# Main.net
KiCad netlist of a schematic drawn in Altium Designer
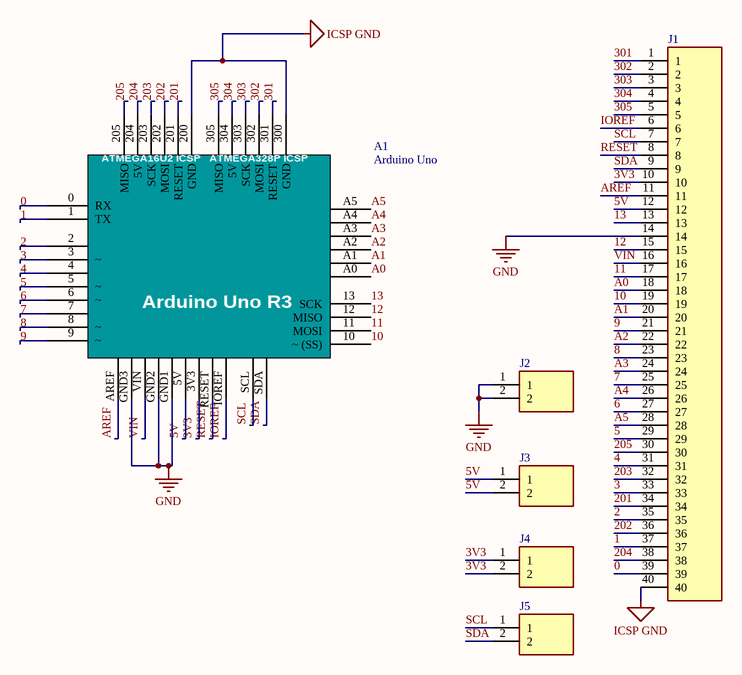
[diagram p0: Main.SchDoc]

(export (version "E")
  (design (tool "Eeschema 10.0.6"))
  (components
    (comp (ref "A1")
      (value "Arduino Uno")
      (footprint "Arduino Uno")
      (libsource (lib "Detailed Arduino") (part "Arduino Uno"))
    )
    (comp (ref "J1")
      (value "1-1761681-3")
      (footprint "TE_1-1761681-3")
      (description "40 Pin Connector")
      (libsource (lib "Molex 40pin Connector") (part "1-1761681-3"))
    )
    (comp (ref "J2")
      (value "TB002-500-02BE")
      (footprint "SamacSys:TB00250002BE")
      (description "Connector")
      (fields (field (name "MOUSER PART NUMBER") "490-TB002-500-02BE"))
      (libsource (lib "SamacSys") (part "TB002-500-02BE"))
    )
    (comp (ref "J3")
      (value "TB002-500-02BE")
      (footprint "SamacSys:TB00250002BE")
      (description "Connector")
      (fields (field (name "MOUSER PART NUMBER") "490-TB002-500-02BE"))
      (libsource (lib "SamacSys") (part "TB002-500-02BE"))
    )
    (comp (ref "J4")
      (value "TB002-500-02BE")
      (footprint "SamacSys:TB00250002BE")
      (description "Connector")
      (fields (field (name "MOUSER PART NUMBER") "490-TB002-500-02BE"))
      (libsource (lib "SamacSys") (part "TB002-500-02BE"))
    )
    (comp (ref "J5")
      (value "TB002-500-02BE")
      (footprint "SamacSys:TB00250002BE")
      (description "Connector")
      (fields (field (name "MOUSER PART NUMBER") "490-TB002-500-02BE"))
      (libsource (lib "SamacSys") (part "TB002-500-02BE"))
    )
  )
  (nets
    (net (code "1") (name "/0") (class "Default")
      (node (ref "A1") (pin "0") (pinfunction "RX_0") (pintype "power_in"))
      (node (ref "J1") (pin "39") (pinfunction "39_39") (pintype "passive"))
    )
    (net (code "2") (name "/1") (class "Default")
      (node (ref "A1") (pin "1") (pinfunction "TX_1") (pintype "power_in"))
      (node (ref "J1") (pin "37") (pinfunction "37_37") (pintype "passive"))
    )
    (net (code "3") (name "/2") (class "Default")
      (node (ref "A1") (pin "2") (pintype "power_in"))
      (node (ref "J1") (pin "35") (pinfunction "35_35") (pintype "passive"))
    )
    (net (code "4") (name "/3") (class "Default")
      (node (ref "A1") (pin "3") (pinfunction "~_3") (pintype "power_in"))
      (node (ref "J1") (pin "33") (pinfunction "33_33") (pintype "passive"))
    )
    (net (code "5") (name "/3V3") (class "Default")
      (node (ref "A1") (pin "3V3") (pintype "power_in"))
      (node (ref "J1") (pin "10") (pinfunction "10_10") (pintype "passive"))
      (node (ref "J4") (pin "1") (pinfunction "1_1") (pintype "passive"))
      (node (ref "J4") (pin "2") (pinfunction "2_2") (pintype "passive"))
    )
    (net (code "6") (name "/4") (class "Default")
      (node (ref "A1") (pin "4") (pintype "power_in"))
      (node (ref "J1") (pin "31") (pinfunction "31_31") (pintype "passive"))
    )
    (net (code "7") (name "/5") (class "Default")
      (node (ref "A1") (pin "5") (pinfunction "~_5") (pintype "power_in"))
      (node (ref "J1") (pin "29") (pinfunction "29_29") (pintype "passive"))
    )
    (net (code "8") (name "/5V") (class "Default")
      (node (ref "A1") (pin "5V") (pintype "power_in"))
      (node (ref "J1") (pin "12") (pinfunction "12_12") (pintype "passive"))
      (node (ref "J3") (pin "1") (pinfunction "1_1") (pintype "passive"))
      (node (ref "J3") (pin "2") (pinfunction "2_2") (pintype "passive"))
    )
    (net (code "9") (name "/6") (class "Default")
      (node (ref "A1") (pin "6") (pinfunction "~_6") (pintype "power_in"))
      (node (ref "J1") (pin "27") (pinfunction "27_27") (pintype "passive"))
    )
    (net (code "10") (name "/7") (class "Default")
      (node (ref "A1") (pin "7") (pintype "power_in"))
      (node (ref "J1") (pin "25") (pinfunction "25_25") (pintype "passive"))
    )
    (net (code "11") (name "/8") (class "Default")
      (node (ref "A1") (pin "8") (pinfunction "~_8") (pintype "power_in"))
      (node (ref "J1") (pin "23") (pinfunction "23_23") (pintype "passive"))
    )
    (net (code "12") (name "/9") (class "Default")
      (node (ref "A1") (pin "9") (pinfunction "~_9") (pintype "power_in"))
      (node (ref "J1") (pin "21") (pinfunction "21_21") (pintype "passive"))
    )
    (net (code "13") (name "/10") (class "Default")
      (node (ref "A1") (pin "10") (pinfunction "~_(SS)_10") (pintype "power_in"))
      (node (ref "J1") (pin "19") (pinfunction "19_19") (pintype "passive"))
    )
    (net (code "14") (name "/11") (class "Default")
      (node (ref "A1") (pin "11") (pinfunction "MOSI_11") (pintype "power_in"))
      (node (ref "J1") (pin "17") (pinfunction "17_17") (pintype "passive"))
    )
    (net (code "15") (name "/12") (class "Default")
      (node (ref "A1") (pin "12") (pinfunction "MISO_12") (pintype "power_in"))
      (node (ref "J1") (pin "15") (pinfunction "15_15") (pintype "passive"))
    )
    (net (code "16") (name "/13") (class "Default")
      (node (ref "A1") (pin "13") (pinfunction "SCK_13") (pintype "power_in"))
      (node (ref "J1") (pin "13") (pinfunction "13_13") (pintype "passive"))
    )
    (net (code "17") (name "/201") (class "Default")
      (node (ref "A1") (pin "201") (pinfunction "RESET_201") (pintype "power_in"))
      (node (ref "J1") (pin "34") (pinfunction "34_34") (pintype "passive"))
    )
    (net (code "18") (name "/202") (class "Default")
      (node (ref "A1") (pin "202") (pinfunction "MOSI_202") (pintype "power_in"))
      (node (ref "J1") (pin "36") (pinfunction "36_36") (pintype "passive"))
    )
    (net (code "19") (name "/203") (class "Default")
      (node (ref "A1") (pin "203") (pinfunction "SCK_203") (pintype "power_in"))
      (node (ref "J1") (pin "32") (pinfunction "32_32") (pintype "passive"))
    )
    (net (code "20") (name "/204") (class "Default")
      (node (ref "A1") (pin "204") (pinfunction "5V_204") (pintype "power_in"))
      (node (ref "J1") (pin "38") (pinfunction "38_38") (pintype "passive"))
    )
    (net (code "21") (name "/205") (class "Default")
      (node (ref "A1") (pin "205") (pinfunction "MISO_205") (pintype "power_in"))
      (node (ref "J1") (pin "30") (pinfunction "30_30") (pintype "passive"))
    )
    (net (code "22") (name "/301") (class "Default")
      (node (ref "A1") (pin "301") (pinfunction "RESET_301") (pintype "power_in"))
      (node (ref "J1") (pin "1") (pinfunction "1_1") (pintype "passive"))
    )
    (net (code "23") (name "/302") (class "Default")
      (node (ref "A1") (pin "302") (pinfunction "MOSI_302") (pintype "power_in"))
      (node (ref "J1") (pin "2") (pinfunction "2_2") (pintype "passive"))
    )
    (net (code "24") (name "/303") (class "Default")
      (node (ref "A1") (pin "303") (pinfunction "SCK_303") (pintype "power_in"))
      (node (ref "J1") (pin "3") (pinfunction "3_3") (pintype "passive"))
    )
    (net (code "25") (name "/304") (class "Default")
      (node (ref "A1") (pin "304") (pinfunction "5V_304") (pintype "power_in"))
      (node (ref "J1") (pin "4") (pinfunction "4_4") (pintype "passive"))
    )
    (net (code "26") (name "/305") (class "Default")
      (node (ref "A1") (pin "305") (pinfunction "MISO_305") (pintype "power_in"))
      (node (ref "J1") (pin "5") (pinfunction "5_5") (pintype "passive"))
    )
    (net (code "27") (name "/A0") (class "Default")
      (node (ref "A1") (pin "A0") (pintype "power_in"))
      (node (ref "J1") (pin "18") (pinfunction "18_18") (pintype "passive"))
    )
    (net (code "28") (name "/A1") (class "Default")
      (node (ref "A1") (pin "A1") (pintype "power_in"))
      (node (ref "J1") (pin "20") (pinfunction "20_20") (pintype "passive"))
    )
    (net (code "29") (name "/A2") (class "Default")
      (node (ref "A1") (pin "A2") (pintype "power_in"))
      (node (ref "J1") (pin "22") (pinfunction "22_22") (pintype "passive"))
    )
    (net (code "30") (name "/A3") (class "Default")
      (node (ref "A1") (pin "A3") (pintype "power_in"))
      (node (ref "J1") (pin "24") (pinfunction "24_24") (pintype "passive"))
    )
    (net (code "31") (name "/A4") (class "Default")
      (node (ref "A1") (pin "A4") (pintype "power_in"))
      (node (ref "J1") (pin "26") (pinfunction "26_26") (pintype "passive"))
    )
    (net (code "32") (name "/A5") (class "Default")
      (node (ref "A1") (pin "A5") (pintype "power_in"))
      (node (ref "J1") (pin "28") (pinfunction "28_28") (pintype "passive"))
    )
    (net (code "33") (name "/AREF") (class "Default")
      (node (ref "A1") (pin "AREF") (pintype "power_in"))
      (node (ref "J1") (pin "11") (pinfunction "11_11") (pintype "passive"))
    )
    (net (code "34") (name "/IOREF") (class "Default")
      (node (ref "A1") (pin "IOREF") (pintype "power_in"))
      (node (ref "J1") (pin "6") (pinfunction "6_6") (pintype "passive"))
    )
    (net (code "35") (name "/RESET") (class "Default")
      (node (ref "A1") (pin "RESET") (pintype "power_in"))
      (node (ref "J1") (pin "8") (pinfunction "8_8") (pintype "passive"))
    )
    (net (code "36") (name "/SCL") (class "Default")
      (node (ref "A1") (pin "SCL") (pintype "power_in"))
      (node (ref "J1") (pin "7") (pinfunction "7_7") (pintype "passive"))
      (node (ref "J5") (pin "1") (pinfunction "1_1") (pintype "passive"))
    )
    (net (code "37") (name "/SDA") (class "Default")
      (node (ref "A1") (pin "SDA") (pintype "power_in"))
      (node (ref "J1") (pin "9") (pinfunction "9_9") (pintype "passive"))
      (node (ref "J5") (pin "2") (pinfunction "2_2") (pintype "passive"))
    )
    (net (code "38") (name "/VIN") (class "Default")
      (node (ref "A1") (pin "VIN") (pintype "power_in"))
      (node (ref "J1") (pin "16") (pinfunction "16_16") (pintype "passive"))
    )
    (net (code "39") (name "GND") (class "Default")
      (node (ref "A1") (pin "GND1") (pintype "power_in"))
      (node (ref "A1") (pin "GND2") (pintype "power_in"))
      (node (ref "A1") (pin "GND3") (pintype "power_in"))
      (node (ref "J1") (pin "14") (pinfunction "14_14") (pintype "passive"))
      (node (ref "J2") (pin "1") (pinfunction "1_1") (pintype "passive"))
      (node (ref "J2") (pin "2") (pinfunction "2_2") (pintype "passive"))
    )
    (net (code "40") (name "ICSP GND") (class "Default")
      (node (ref "A1") (pin "200") (pinfunction "GND_200") (pintype "power_in"))
      (node (ref "A1") (pin "300") (pinfunction "GND_300") (pintype "power_in"))
      (node (ref "J1") (pin "40") (pinfunction "40_40") (pintype "passive"))
    )
  )
)
